# RGB_Driver.net
KiCad netlist of a schematic drawn in EAGLE
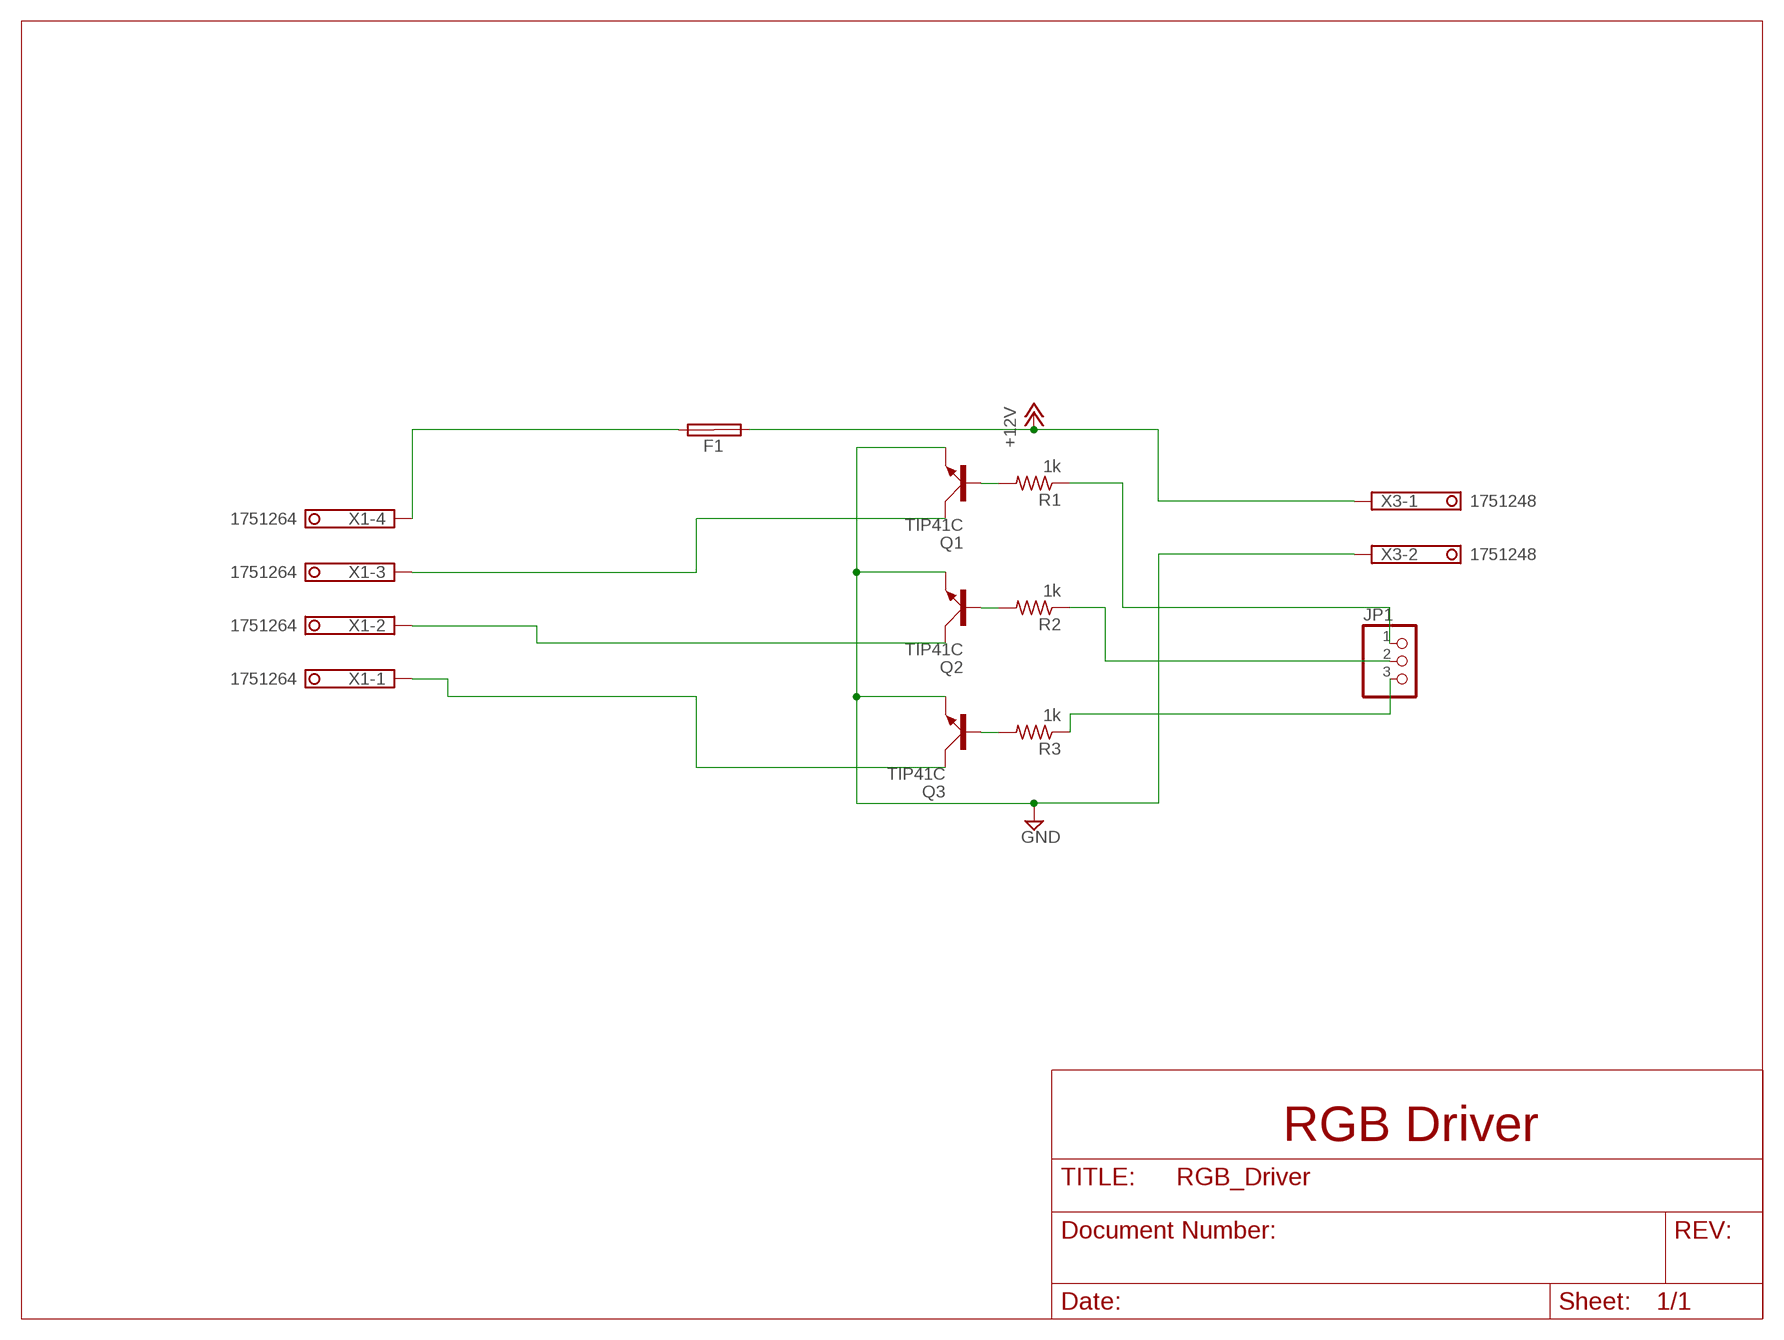
[diagram p0: schematic, sheet 1]

(export (version "E")
  (design (tool "Eeschema 10.0.6"))
  (components
    (comp (ref "F1")
      (value "SHK20L")
      (footprint "eagle-import:SHK20L")
      (libsource (lib "eagle-import") (part "SHK20L"))
    )
    (comp (ref "JP1")
      (value "PINHD-1X3")
      (footprint "eagle-import:1X03")
      (libsource (lib "eagle-import") (part "PINHD-1X3"))
    )
    (comp (ref "Q1")
      (value "TIP41C")
      (footprint "eagle-import:TO220AV")
      (libsource (lib "eagle-import") (part "TIP41C"))
    )
    (comp (ref "Q2")
      (value "TIP41C")
      (footprint "eagle-import:TO220AV")
      (libsource (lib "eagle-import") (part "TIP41C"))
    )
    (comp (ref "Q3")
      (value "TIP41C")
      (footprint "eagle-import:TO220AV")
      (libsource (lib "eagle-import") (part "TIP41C"))
    )
    (comp (ref "R1")
      (value "1k")
      (footprint "eagle-import:0204_7")
      (libsource (lib "eagle-import") (part "R-US_0204/7"))
    )
    (comp (ref "R2")
      (value "1k")
      (footprint "eagle-import:0204_7")
      (libsource (lib "eagle-import") (part "R-US_0204/7"))
    )
    (comp (ref "R3")
      (value "1k")
      (footprint "eagle-import:0204_7")
      (libsource (lib "eagle-import") (part "R-US_0204/7"))
    )
    (comp (ref "X1")
      (value "1751264")
      (footprint "eagle-import:1751264")
      (libsource (lib "eagle-import") (part "1751264"))
    )
    (comp (ref "X3")
      (value "1751248")
      (footprint "eagle-import:1751248")
      (libsource (lib "eagle-import") (part "1751248"))
    )
  )
  (nets
    (net (code "1") (name "+12V") (class "Default")
      (node (ref "F1") (pin "1A") (pinfunction "1A_1A") (pintype "passive"))
      (node (ref "X3") (pin "1") (pinfunction "K_1") (pintype "passive"))
    )
    (net (code "2") (name "GND") (class "Default")
      (node (ref "Q1") (pin "E") (pinfunction "E_E") (pintype "passive"))
      (node (ref "Q2") (pin "E") (pinfunction "E_E") (pintype "passive"))
      (node (ref "Q3") (pin "E") (pinfunction "E_E") (pintype "passive"))
      (node (ref "X3") (pin "2") (pinfunction "K_2") (pintype "passive"))
    )
    (net (code "3") (name "Net-(JP1-Pad1)") (class "Default")
      (node (ref "JP1") (pin "1") (pinfunction "1_1") (pintype "passive"))
      (node (ref "R1") (pin "1") (pinfunction "1_1") (pintype "passive"))
    )
    (net (code "4") (name "Net-(JP1-Pad2)") (class "Default")
      (node (ref "JP1") (pin "2") (pinfunction "2_2") (pintype "passive"))
      (node (ref "R2") (pin "1") (pinfunction "1_1") (pintype "passive"))
    )
    (net (code "5") (name "Net-(JP1-Pad3)") (class "Default")
      (node (ref "JP1") (pin "3") (pinfunction "3_3") (pintype "passive"))
      (node (ref "R3") (pin "1") (pinfunction "1_1") (pintype "passive"))
    )
    (net (code "6") (name "Net-(Q1-PadB)") (class "Default")
      (node (ref "Q1") (pin "B") (pinfunction "B_B") (pintype "passive"))
      (node (ref "R1") (pin "2") (pinfunction "2_2") (pintype "passive"))
    )
    (net (code "7") (name "Net-(Q2-PadB)") (class "Default")
      (node (ref "Q2") (pin "B") (pinfunction "B_B") (pintype "passive"))
      (node (ref "R2") (pin "2") (pinfunction "2_2") (pintype "passive"))
    )
    (net (code "8") (name "Net-(Q3-PadB)") (class "Default")
      (node (ref "Q3") (pin "B") (pinfunction "B_B") (pintype "passive"))
      (node (ref "R3") (pin "2") (pinfunction "2_2") (pintype "passive"))
    )
    (net (code "9") (name "Net-(X1A-K)") (class "Default")
      (node (ref "Q3") (pin "C") (pinfunction "C_C") (pintype "passive"))
      (node (ref "X1") (pin "1") (pinfunction "K_1") (pintype "passive"))
    )
    (net (code "10") (name "Net-(X1B-K)") (class "Default")
      (node (ref "Q2") (pin "C") (pinfunction "C_C") (pintype "passive"))
      (node (ref "X1") (pin "2") (pinfunction "K_2") (pintype "passive"))
    )
    (net (code "11") (name "Net-(X1C-K)") (class "Default")
      (node (ref "Q1") (pin "C") (pinfunction "C_C") (pintype "passive"))
      (node (ref "X1") (pin "3") (pinfunction "K_3") (pintype "passive"))
    )
    (net (code "12") (name "Net-(X1D-K)") (class "Default")
      (node (ref "F1") (pin "2A") (pinfunction "2A_2A") (pintype "passive"))
      (node (ref "X1") (pin "4") (pinfunction "K_4") (pintype "passive"))
    )
    (net (code "13") (name "unconnected-(F1-Pad1B)") (class "Default")
      (node (ref "F1") (pin "1B") (pinfunction "1B_1B") (pintype "passive"))
    )
    (net (code "14") (name "unconnected-(F1-Pad2B)") (class "Default")
      (node (ref "F1") (pin "2B") (pinfunction "2B_2B") (pintype "passive"))
    )
  )
)
